# 2x3AND_OR_1.net
KiCad netlist of a schematic drawn in EAGLE
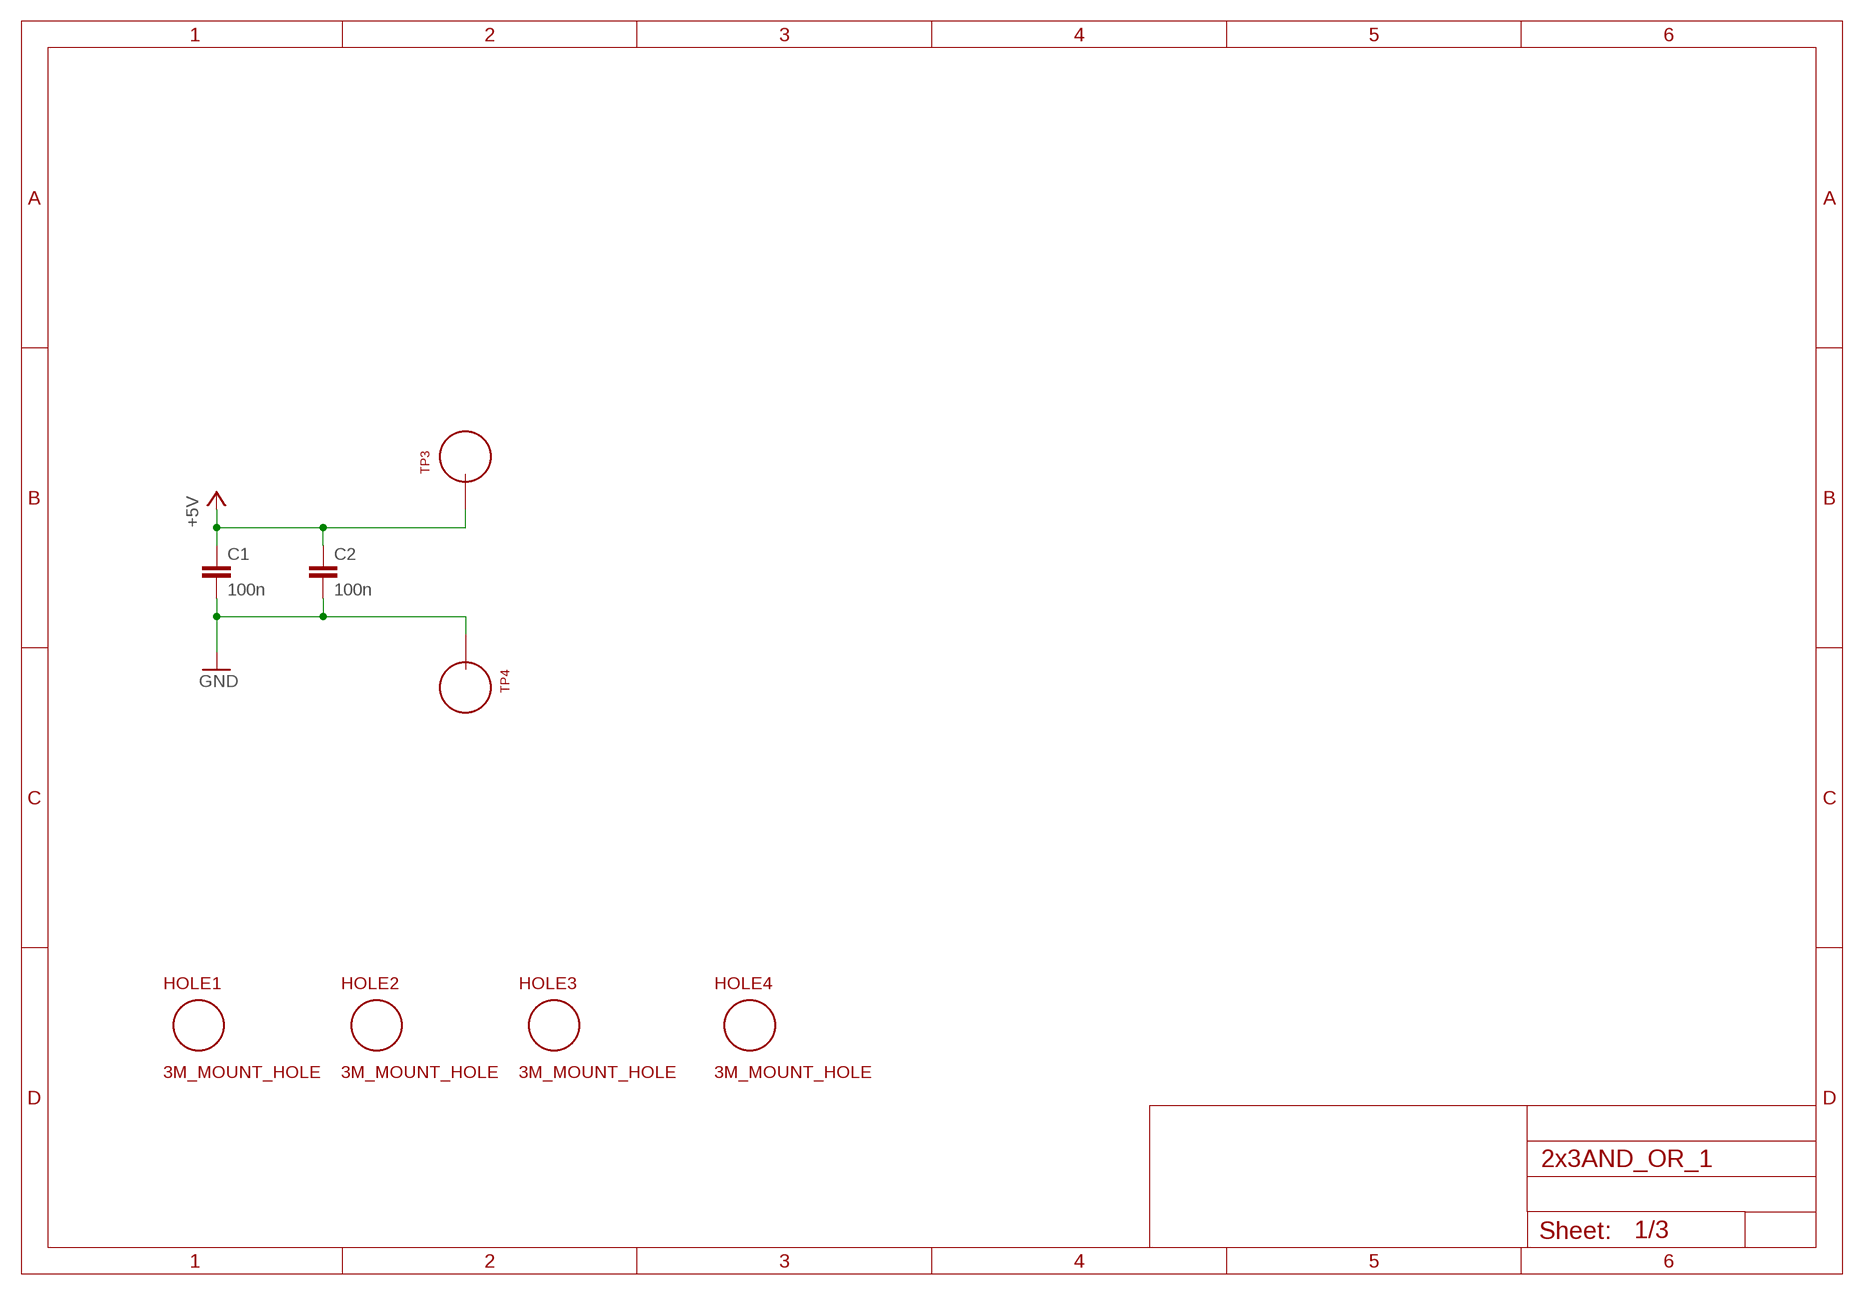
[diagram p0: schematic, sheet 1]
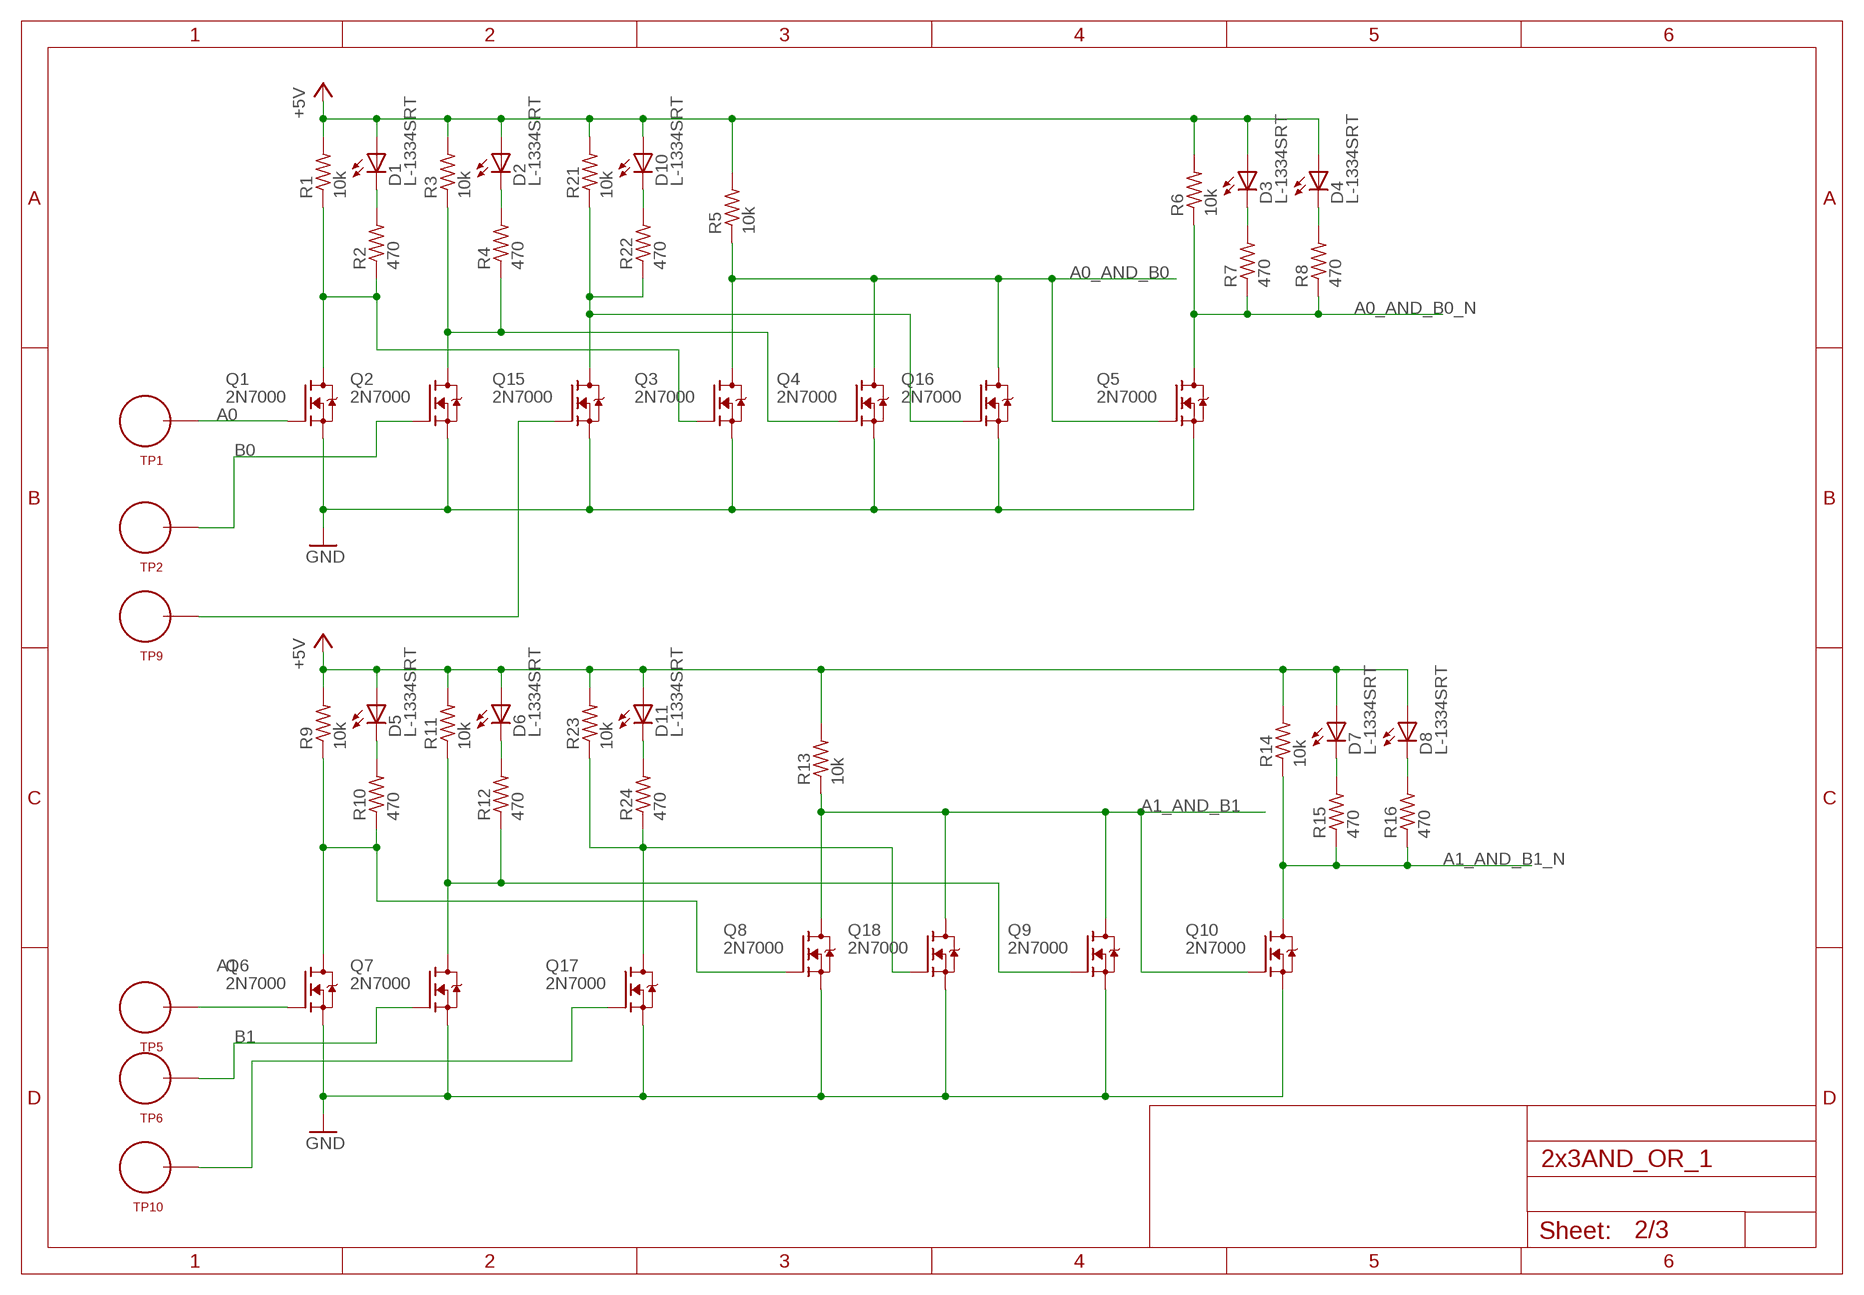
[diagram p1: schematic, sheet 2]
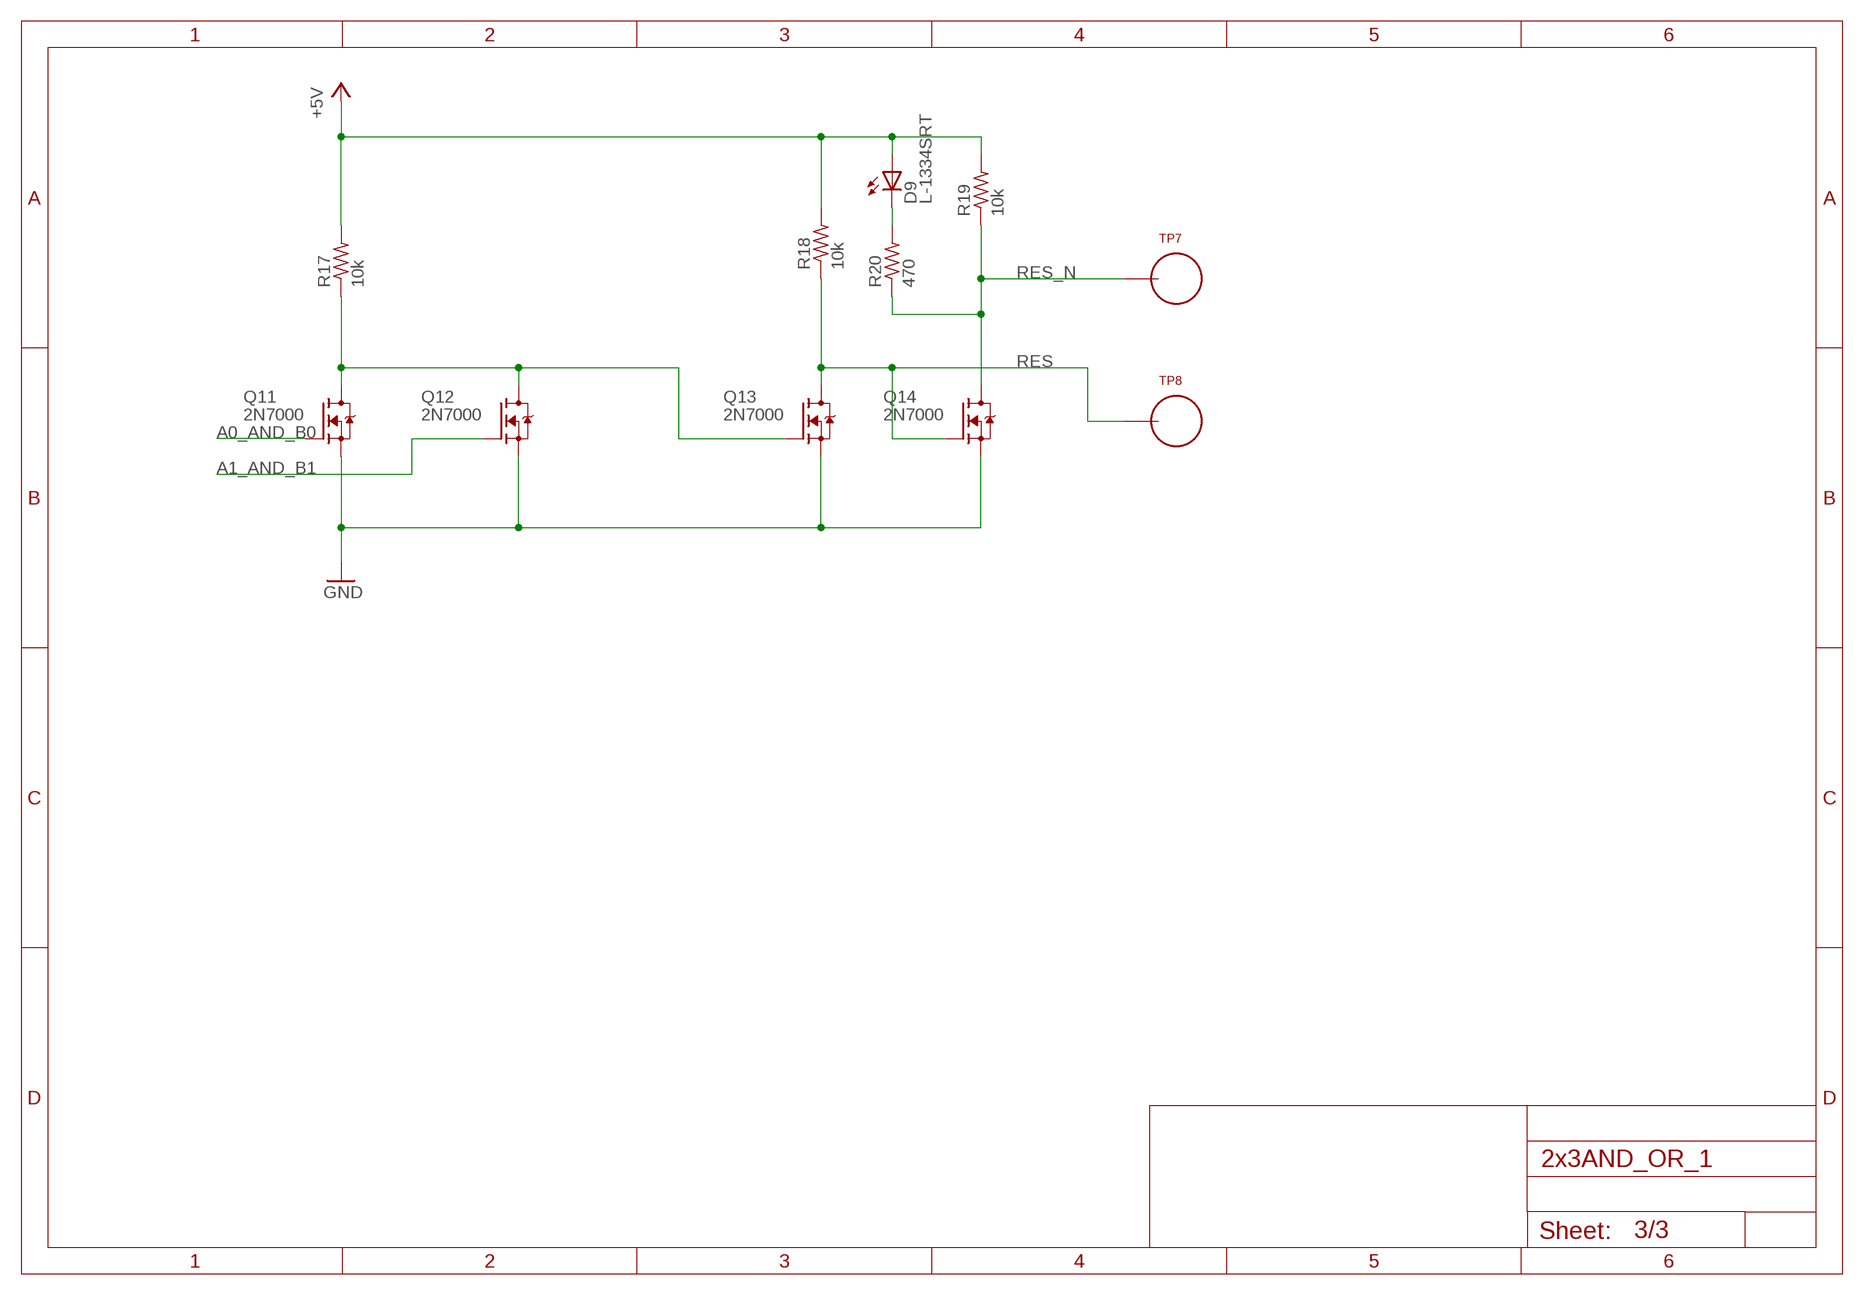
[diagram p2: schematic, sheet 3]

(export (version "E")
  (design (tool "Eeschema 10.0.6"))
  (components
    (comp (ref "D1")
      (value "L-1334SRT")
      (footprint "eagle-import:LED3MM")
      (libsource (lib "eagle-import") (part "L-1334SRT"))
    )
    (comp (ref "D2")
      (value "L-1334SRT")
      (footprint "eagle-import:LED3MM")
      (libsource (lib "eagle-import") (part "L-1334SRT"))
    )
    (comp (ref "D3")
      (value "L-1334SRT")
      (footprint "eagle-import:LED3MM")
      (libsource (lib "eagle-import") (part "L-1334SRT"))
    )
    (comp (ref "D4")
      (value "L-1334SRT")
      (footprint "eagle-import:LED3MM")
      (libsource (lib "eagle-import") (part "L-1334SRT"))
    )
    (comp (ref "D5")
      (value "L-1334SRT")
      (footprint "eagle-import:LED3MM")
      (libsource (lib "eagle-import") (part "L-1334SRT"))
    )
    (comp (ref "D6")
      (value "L-1334SRT")
      (footprint "eagle-import:LED3MM")
      (libsource (lib "eagle-import") (part "L-1334SRT"))
    )
    (comp (ref "D7")
      (value "L-1334SRT")
      (footprint "eagle-import:LED3MM")
      (libsource (lib "eagle-import") (part "L-1334SRT"))
    )
    (comp (ref "D8")
      (value "L-1334SRT")
      (footprint "eagle-import:LED3MM")
      (libsource (lib "eagle-import") (part "L-1334SRT"))
    )
    (comp (ref "D10")
      (value "L-1334SRT")
      (footprint "eagle-import:LED3MM")
      (libsource (lib "eagle-import") (part "L-1334SRT"))
    )
    (comp (ref "D11")
      (value "L-1334SRT")
      (footprint "eagle-import:LED3MM")
      (libsource (lib "eagle-import") (part "L-1334SRT"))
    )
    (comp (ref "Q1")
      (value "2N7000")
      (footprint "eagle-import:TO92-DGS")
      (libsource (lib "eagle-import") (part "2N7000"))
    )
    (comp (ref "Q2")
      (value "2N7000")
      (footprint "eagle-import:TO92-DGS")
      (libsource (lib "eagle-import") (part "2N7000"))
    )
    (comp (ref "Q3")
      (value "2N7000")
      (footprint "eagle-import:TO92-DGS")
      (libsource (lib "eagle-import") (part "2N7000"))
    )
    (comp (ref "Q4")
      (value "2N7000")
      (footprint "eagle-import:TO92-DGS")
      (libsource (lib "eagle-import") (part "2N7000"))
    )
    (comp (ref "Q5")
      (value "2N7000")
      (footprint "eagle-import:TO92-DGS")
      (libsource (lib "eagle-import") (part "2N7000"))
    )
    (comp (ref "Q6")
      (value "2N7000")
      (footprint "eagle-import:TO92-DGS")
      (libsource (lib "eagle-import") (part "2N7000"))
    )
    (comp (ref "Q7")
      (value "2N7000")
      (footprint "eagle-import:TO92-DGS")
      (libsource (lib "eagle-import") (part "2N7000"))
    )
    (comp (ref "Q8")
      (value "2N7000")
      (footprint "eagle-import:TO92-DGS")
      (libsource (lib "eagle-import") (part "2N7000"))
    )
    (comp (ref "Q9")
      (value "2N7000")
      (footprint "eagle-import:TO92-DGS")
      (libsource (lib "eagle-import") (part "2N7000"))
    )
    (comp (ref "Q10")
      (value "2N7000")
      (footprint "eagle-import:TO92-DGS")
      (libsource (lib "eagle-import") (part "2N7000"))
    )
    (comp (ref "Q15")
      (value "2N7000")
      (footprint "eagle-import:TO92-DGS")
      (libsource (lib "eagle-import") (part "2N7000"))
    )
    (comp (ref "Q16")
      (value "2N7000")
      (footprint "eagle-import:TO92-DGS")
      (libsource (lib "eagle-import") (part "2N7000"))
    )
    (comp (ref "Q17")
      (value "2N7000")
      (footprint "eagle-import:TO92-DGS")
      (libsource (lib "eagle-import") (part "2N7000"))
    )
    (comp (ref "Q18")
      (value "2N7000")
      (footprint "eagle-import:TO92-DGS")
      (libsource (lib "eagle-import") (part "2N7000"))
    )
    (comp (ref "R1")
      (value "10k")
      (footprint "eagle-import:R_P2INCH")
      (libsource (lib "eagle-import") (part "R_P2INCH"))
    )
    (comp (ref "R2")
      (value "470")
      (footprint "eagle-import:R_P2INCH")
      (libsource (lib "eagle-import") (part "R_P2INCH"))
    )
    (comp (ref "R3")
      (value "10k")
      (footprint "eagle-import:R_P2INCH")
      (libsource (lib "eagle-import") (part "R_P2INCH"))
    )
    (comp (ref "R4")
      (value "470")
      (footprint "eagle-import:R_P2INCH")
      (libsource (lib "eagle-import") (part "R_P2INCH"))
    )
    (comp (ref "R5")
      (value "10k")
      (footprint "eagle-import:R_P2INCH")
      (libsource (lib "eagle-import") (part "R_P2INCH"))
    )
    (comp (ref "R6")
      (value "10k")
      (footprint "eagle-import:R_P2INCH")
      (libsource (lib "eagle-import") (part "R_P2INCH"))
    )
    (comp (ref "R7")
      (value "470")
      (footprint "eagle-import:R_P2INCH")
      (libsource (lib "eagle-import") (part "R_P2INCH"))
    )
    (comp (ref "R8")
      (value "470")
      (footprint "eagle-import:R_P2INCH")
      (libsource (lib "eagle-import") (part "R_P2INCH"))
    )
    (comp (ref "R9")
      (value "10k")
      (footprint "eagle-import:R_P2INCH")
      (libsource (lib "eagle-import") (part "R_P2INCH"))
    )
    (comp (ref "R10")
      (value "470")
      (footprint "eagle-import:R_P2INCH")
      (libsource (lib "eagle-import") (part "R_P2INCH"))
    )
    (comp (ref "R11")
      (value "10k")
      (footprint "eagle-import:R_P2INCH")
      (libsource (lib "eagle-import") (part "R_P2INCH"))
    )
    (comp (ref "R12")
      (value "470")
      (footprint "eagle-import:R_P2INCH")
      (libsource (lib "eagle-import") (part "R_P2INCH"))
    )
    (comp (ref "R13")
      (value "10k")
      (footprint "eagle-import:R_P2INCH")
      (libsource (lib "eagle-import") (part "R_P2INCH"))
    )
    (comp (ref "R14")
      (value "10k")
      (footprint "eagle-import:R_P2INCH")
      (libsource (lib "eagle-import") (part "R_P2INCH"))
    )
    (comp (ref "R15")
      (value "470")
      (footprint "eagle-import:R_P2INCH")
      (libsource (lib "eagle-import") (part "R_P2INCH"))
    )
    (comp (ref "R16")
      (value "470")
      (footprint "eagle-import:R_P2INCH")
      (libsource (lib "eagle-import") (part "R_P2INCH"))
    )
    (comp (ref "R21")
      (value "10k")
      (footprint "eagle-import:R_P2INCH")
      (libsource (lib "eagle-import") (part "R_P2INCH"))
    )
    (comp (ref "R22")
      (value "470")
      (footprint "eagle-import:R_P2INCH")
      (libsource (lib "eagle-import") (part "R_P2INCH"))
    )
    (comp (ref "R23")
      (value "10k")
      (footprint "eagle-import:R_P2INCH")
      (libsource (lib "eagle-import") (part "R_P2INCH"))
    )
    (comp (ref "R24")
      (value "470")
      (footprint "eagle-import:R_P2INCH")
      (libsource (lib "eagle-import") (part "R_P2INCH"))
    )
    (comp (ref "TP1")
      (value "TEST_LOOP")
      (footprint "eagle-import:TEST_LOOP")
      (libsource (lib "eagle-import") (part "TEST_LOOP"))
    )
    (comp (ref "TP2")
      (value "TEST_LOOP")
      (footprint "eagle-import:TEST_LOOP")
      (libsource (lib "eagle-import") (part "TEST_LOOP"))
    )
    (comp (ref "TP5")
      (value "TEST_LOOP")
      (footprint "eagle-import:TEST_LOOP")
      (libsource (lib "eagle-import") (part "TEST_LOOP"))
    )
    (comp (ref "TP6")
      (value "TEST_LOOP")
      (footprint "eagle-import:TEST_LOOP")
      (libsource (lib "eagle-import") (part "TEST_LOOP"))
    )
    (comp (ref "TP9")
      (value "TEST_LOOP")
      (footprint "eagle-import:TEST_LOOP")
      (libsource (lib "eagle-import") (part "TEST_LOOP"))
    )
    (comp (ref "TP10")
      (value "TEST_LOOP")
      (footprint "eagle-import:TEST_LOOP")
      (libsource (lib "eagle-import") (part "TEST_LOOP"))
    )
    (comp (ref "D9")
      (value "L-1334SRT")
      (footprint "eagle-import:LED3MM")
      (libsource (lib "eagle-import") (part "L-1334SRT"))
    )
    (comp (ref "Q11")
      (value "2N7000")
      (footprint "eagle-import:TO92-DGS")
      (libsource (lib "eagle-import") (part "2N7000"))
    )
    (comp (ref "Q12")
      (value "2N7000")
      (footprint "eagle-import:TO92-DGS")
      (libsource (lib "eagle-import") (part "2N7000"))
    )
    (comp (ref "Q13")
      (value "2N7000")
      (footprint "eagle-import:TO92-DGS")
      (libsource (lib "eagle-import") (part "2N7000"))
    )
    (comp (ref "Q14")
      (value "2N7000")
      (footprint "eagle-import:TO92-DGS")
      (libsource (lib "eagle-import") (part "2N7000"))
    )
    (comp (ref "R17")
      (value "10k")
      (footprint "eagle-import:R_P2INCH")
      (libsource (lib "eagle-import") (part "R_P2INCH"))
    )
    (comp (ref "R18")
      (value "10k")
      (footprint "eagle-import:R_P2INCH")
      (libsource (lib "eagle-import") (part "R_P2INCH"))
    )
    (comp (ref "R19")
      (value "10k")
      (footprint "eagle-import:R_P2INCH")
      (libsource (lib "eagle-import") (part "R_P2INCH"))
    )
    (comp (ref "R20")
      (value "470")
      (footprint "eagle-import:R_P2INCH")
      (libsource (lib "eagle-import") (part "R_P2INCH"))
    )
    (comp (ref "TP7")
      (value "TEST_LOOP")
      (footprint "eagle-import:TEST_LOOP")
      (libsource (lib "eagle-import") (part "TEST_LOOP"))
    )
    (comp (ref "TP8")
      (value "TEST_LOOP")
      (footprint "eagle-import:TEST_LOOP")
      (libsource (lib "eagle-import") (part "TEST_LOOP"))
    )
    (comp (ref "C1")
      (value "100n")
      (footprint "eagle-import:CAP_P2INCH")
      (libsource (lib "eagle-import") (part "C_P2INCH"))
    )
    (comp (ref "C2")
      (value "100n")
      (footprint "eagle-import:CAP_P2INCH")
      (libsource (lib "eagle-import") (part "C_P2INCH"))
    )
    (comp (ref "HOLE1")
      (value "3M_MOUNT_HOLE")
      (footprint "eagle-import:3M_HOLE")
      (libsource (lib "eagle-import") (part "3M_MOUNT_HOLE"))
    )
    (comp (ref "HOLE2")
      (value "3M_MOUNT_HOLE")
      (footprint "eagle-import:3M_HOLE")
      (libsource (lib "eagle-import") (part "3M_MOUNT_HOLE"))
    )
    (comp (ref "HOLE3")
      (value "3M_MOUNT_HOLE")
      (footprint "eagle-import:3M_HOLE")
      (libsource (lib "eagle-import") (part "3M_MOUNT_HOLE"))
    )
    (comp (ref "HOLE4")
      (value "3M_MOUNT_HOLE")
      (footprint "eagle-import:3M_HOLE")
      (libsource (lib "eagle-import") (part "3M_MOUNT_HOLE"))
    )
    (comp (ref "TP3")
      (value "TEST_LOOP")
      (footprint "eagle-import:TEST_LOOP")
      (libsource (lib "eagle-import") (part "TEST_LOOP"))
    )
    (comp (ref "TP4")
      (value "TEST_LOOP")
      (footprint "eagle-import:TEST_LOOP")
      (libsource (lib "eagle-import") (part "TEST_LOOP"))
    )
  )
  (nets
    (net (code "1") (name "+5V") (class "Default")
      (node (ref "C1") (pin "1") (pinfunction "1_1") (pintype "passive"))
      (node (ref "C2") (pin "1") (pinfunction "1_1") (pintype "passive"))
      (node (ref "D1") (pin "A") (pinfunction "A_A") (pintype "passive"))
      (node (ref "D10") (pin "A") (pinfunction "A_A") (pintype "passive"))
      (node (ref "D11") (pin "A") (pinfunction "A_A") (pintype "passive"))
      (node (ref "D2") (pin "A") (pinfunction "A_A") (pintype "passive"))
      (node (ref "D3") (pin "A") (pinfunction "A_A") (pintype "passive"))
      (node (ref "D4") (pin "A") (pinfunction "A_A") (pintype "passive"))
      (node (ref "D5") (pin "A") (pinfunction "A_A") (pintype "passive"))
      (node (ref "D6") (pin "A") (pinfunction "A_A") (pintype "passive"))
      (node (ref "D7") (pin "A") (pinfunction "A_A") (pintype "passive"))
      (node (ref "D8") (pin "A") (pinfunction "A_A") (pintype "passive"))
      (node (ref "D9") (pin "A") (pinfunction "A_A") (pintype "passive"))
      (node (ref "R1") (pin "2") (pinfunction "2_2") (pintype "passive"))
      (node (ref "R11") (pin "2") (pinfunction "2_2") (pintype "passive"))
      (node (ref "R13") (pin "2") (pinfunction "2_2") (pintype "passive"))
      (node (ref "R14") (pin "2") (pinfunction "2_2") (pintype "passive"))
      (node (ref "R17") (pin "2") (pinfunction "2_2") (pintype "passive"))
      (node (ref "R18") (pin "2") (pinfunction "2_2") (pintype "passive"))
      (node (ref "R19") (pin "2") (pinfunction "2_2") (pintype "passive"))
      (node (ref "R21") (pin "2") (pinfunction "2_2") (pintype "passive"))
      (node (ref "R23") (pin "2") (pinfunction "2_2") (pintype "passive"))
      (node (ref "R3") (pin "2") (pinfunction "2_2") (pintype "passive"))
      (node (ref "R5") (pin "2") (pinfunction "2_2") (pintype "passive"))
      (node (ref "R6") (pin "2") (pinfunction "2_2") (pintype "passive"))
      (node (ref "R9") (pin "2") (pinfunction "2_2") (pintype "passive"))
      (node (ref "TP3") (pin "P$1") (pinfunction "P$1_P$1") (pintype "bidirectional"))
    )
    (net (code "2") (name "A0") (class "Default")
      (node (ref "Q1") (pin "G") (pinfunction "G_G") (pintype "passive"))
      (node (ref "TP1") (pin "P$1") (pinfunction "P$1_P$1") (pintype "bidirectional"))
    )
    (net (code "3") (name "A0_AND_B0") (class "Default")
      (node (ref "Q11") (pin "G") (pinfunction "G_G") (pintype "passive"))
      (node (ref "Q16") (pin "D") (pinfunction "D_D") (pintype "passive"))
      (node (ref "Q3") (pin "D") (pinfunction "D_D") (pintype "passive"))
      (node (ref "Q4") (pin "D") (pinfunction "D_D") (pintype "passive"))
      (node (ref "Q5") (pin "G") (pinfunction "G_G") (pintype "passive"))
      (node (ref "R5") (pin "1") (pinfunction "1_1") (pintype "passive"))
    )
    (net (code "4") (name "A0_AND_B0_N") (class "Default")
      (node (ref "Q5") (pin "D") (pinfunction "D_D") (pintype "passive"))
      (node (ref "R6") (pin "1") (pinfunction "1_1") (pintype "passive"))
      (node (ref "R7") (pin "1") (pinfunction "1_1") (pintype "passive"))
      (node (ref "R8") (pin "1") (pinfunction "1_1") (pintype "passive"))
    )
    (net (code "5") (name "A1") (class "Default")
      (node (ref "Q6") (pin "G") (pinfunction "G_G") (pintype "passive"))
      (node (ref "TP5") (pin "P$1") (pinfunction "P$1_P$1") (pintype "bidirectional"))
    )
    (net (code "6") (name "A1_AND_B1") (class "Default")
      (node (ref "Q10") (pin "G") (pinfunction "G_G") (pintype "passive"))
      (node (ref "Q12") (pin "G") (pinfunction "G_G") (pintype "passive"))
      (node (ref "Q18") (pin "D") (pinfunction "D_D") (pintype "passive"))
      (node (ref "Q8") (pin "D") (pinfunction "D_D") (pintype "passive"))
      (node (ref "Q9") (pin "D") (pinfunction "D_D") (pintype "passive"))
      (node (ref "R13") (pin "1") (pinfunction "1_1") (pintype "passive"))
    )
    (net (code "7") (name "A1_AND_B1_N") (class "Default")
      (node (ref "Q10") (pin "D") (pinfunction "D_D") (pintype "passive"))
      (node (ref "R14") (pin "1") (pinfunction "1_1") (pintype "passive"))
      (node (ref "R15") (pin "1") (pinfunction "1_1") (pintype "passive"))
      (node (ref "R16") (pin "1") (pinfunction "1_1") (pintype "passive"))
    )
    (net (code "8") (name "B0") (class "Default")
      (node (ref "Q2") (pin "G") (pinfunction "G_G") (pintype "passive"))
      (node (ref "TP2") (pin "P$1") (pinfunction "P$1_P$1") (pintype "bidirectional"))
    )
    (net (code "9") (name "B1") (class "Default")
      (node (ref "Q7") (pin "G") (pinfunction "G_G") (pintype "passive"))
      (node (ref "TP6") (pin "P$1") (pinfunction "P$1_P$1") (pintype "bidirectional"))
    )
    (net (code "10") (name "GND") (class "Default")
      (node (ref "C1") (pin "2") (pinfunction "2_2") (pintype "passive"))
      (node (ref "C2") (pin "2") (pinfunction "2_2") (pintype "passive"))
      (node (ref "Q1") (pin "S") (pinfunction "S_S") (pintype "passive"))
      (node (ref "Q10") (pin "S") (pinfunction "S_S") (pintype "passive"))
      (node (ref "Q11") (pin "S") (pinfunction "S_S") (pintype "passive"))
      (node (ref "Q12") (pin "S") (pinfunction "S_S") (pintype "passive"))
      (node (ref "Q13") (pin "S") (pinfunction "S_S") (pintype "passive"))
      (node (ref "Q14") (pin "S") (pinfunction "S_S") (pintype "passive"))
      (node (ref "Q15") (pin "S") (pinfunction "S_S") (pintype "passive"))
      (node (ref "Q16") (pin "S") (pinfunction "S_S") (pintype "passive"))
      (node (ref "Q17") (pin "S") (pinfunction "S_S") (pintype "passive"))
      (node (ref "Q18") (pin "S") (pinfunction "S_S") (pintype "passive"))
      (node (ref "Q2") (pin "S") (pinfunction "S_S") (pintype "passive"))
      (node (ref "Q3") (pin "S") (pinfunction "S_S") (pintype "passive"))
      (node (ref "Q4") (pin "S") (pinfunction "S_S") (pintype "passive"))
      (node (ref "Q5") (pin "S") (pinfunction "S_S") (pintype "passive"))
      (node (ref "Q6") (pin "S") (pinfunction "S_S") (pintype "passive"))
      (node (ref "Q7") (pin "S") (pinfunction "S_S") (pintype "passive"))
      (node (ref "Q8") (pin "S") (pinfunction "S_S") (pintype "passive"))
      (node (ref "Q9") (pin "S") (pinfunction "S_S") (pintype "passive"))
      (node (ref "TP4") (pin "P$1") (pinfunction "P$1_P$1") (pintype "bidirectional"))
    )
    (net (code "11") (name "Net-(D1-C)") (class "Default")
      (node (ref "D1") (pin "K") (pinfunction "C_K") (pintype "passive"))
      (node (ref "R2") (pin "2") (pinfunction "2_2") (pintype "passive"))
    )
    (net (code "12") (name "Net-(D2-C)") (class "Default")
      (node (ref "D2") (pin "K") (pinfunction "C_K") (pintype "passive"))
      (node (ref "R4") (pin "2") (pinfunction "2_2") (pintype "passive"))
    )
    (net (code "13") (name "Net-(D3-C)") (class "Default")
      (node (ref "D3") (pin "K") (pinfunction "C_K") (pintype "passive"))
      (node (ref "R7") (pin "2") (pinfunction "2_2") (pintype "passive"))
    )
    (net (code "14") (name "Net-(D4-C)") (class "Default")
      (node (ref "D4") (pin "K") (pinfunction "C_K") (pintype "passive"))
      (node (ref "R8") (pin "2") (pinfunction "2_2") (pintype "passive"))
    )
    (net (code "15") (name "Net-(D5-C)") (class "Default")
      (node (ref "D5") (pin "K") (pinfunction "C_K") (pintype "passive"))
      (node (ref "R10") (pin "2") (pinfunction "2_2") (pintype "passive"))
    )
    (net (code "16") (name "Net-(D6-C)") (class "Default")
      (node (ref "D6") (pin "K") (pinfunction "C_K") (pintype "passive"))
      (node (ref "R12") (pin "2") (pinfunction "2_2") (pintype "passive"))
    )
    (net (code "17") (name "Net-(D7-C)") (class "Default")
      (node (ref "D7") (pin "K") (pinfunction "C_K") (pintype "passive"))
      (node (ref "R15") (pin "2") (pinfunction "2_2") (pintype "passive"))
    )
    (net (code "18") (name "Net-(D8-C)") (class "Default")
      (node (ref "D8") (pin "K") (pinfunction "C_K") (pintype "passive"))
      (node (ref "R16") (pin "2") (pinfunction "2_2") (pintype "passive"))
    )
    (net (code "19") (name "Net-(D9-C)") (class "Default")
      (node (ref "D9") (pin "K") (pinfunction "C_K") (pintype "passive"))
      (node (ref "R20") (pin "2") (pinfunction "2_2") (pintype "passive"))
    )
    (net (code "20") (name "Net-(D10-C)") (class "Default")
      (node (ref "D10") (pin "K") (pinfunction "C_K") (pintype "passive"))
      (node (ref "R22") (pin "2") (pinfunction "2_2") (pintype "passive"))
    )
    (net (code "21") (name "Net-(D11-C)") (class "Default")
      (node (ref "D11") (pin "K") (pinfunction "C_K") (pintype "passive"))
      (node (ref "R24") (pin "2") (pinfunction "2_2") (pintype "passive"))
    )
    (net (code "22") (name "Net-(Q1-PadD)") (class "Default")
      (node (ref "Q1") (pin "D") (pinfunction "D_D") (pintype "passive"))
      (node (ref "Q3") (pin "G") (pinfunction "G_G") (pintype "passive"))
      (node (ref "R1") (pin "1") (pinfunction "1_1") (pintype "passive"))
      (node (ref "R2") (pin "1") (pinfunction "1_1") (pintype "passive"))
    )
    (net (code "23") (name "Net-(Q2-PadD)") (class "Default")
      (node (ref "Q2") (pin "D") (pinfunction "D_D") (pintype "passive"))
      (node (ref "Q4") (pin "G") (pinfunction "G_G") (pintype "passive"))
      (node (ref "R3") (pin "1") (pinfunction "1_1") (pintype "passive"))
      (node (ref "R4") (pin "1") (pinfunction "1_1") (pintype "passive"))
    )
    (net (code "24") (name "Net-(Q6-PadD)") (class "Default")
      (node (ref "Q6") (pin "D") (pinfunction "D_D") (pintype "passive"))
      (node (ref "Q8") (pin "G") (pinfunction "G_G") (pintype "passive"))
      (node (ref "R10") (pin "1") (pinfunction "1_1") (pintype "passive"))
      (node (ref "R9") (pin "1") (pinfunction "1_1") (pintype "passive"))
    )
    (net (code "25") (name "Net-(Q7-PadD)") (class "Default")
      (node (ref "Q7") (pin "D") (pinfunction "D_D") (pintype "passive"))
      (node (ref "Q9") (pin "G") (pinfunction "G_G") (pintype "passive"))
      (node (ref "R11") (pin "1") (pinfunction "1_1") (pintype "passive"))
      (node (ref "R12") (pin "1") (pinfunction "1_1") (pintype "passive"))
    )
    (net (code "26") (name "Net-(Q11-PadD)") (class "Default")
      (node (ref "Q11") (pin "D") (pinfunction "D_D") (pintype "passive"))
      (node (ref "Q12") (pin "D") (pinfunction "D_D") (pintype "passive"))
      (node (ref "Q13") (pin "G") (pinfunction "G_G") (pintype "passive"))
      (node (ref "R17") (pin "1") (pinfunction "1_1") (pintype "passive"))
    )
    (net (code "27") (name "Net-(Q15-PadD)") (class "Default")
      (node (ref "Q15") (pin "D") (pinfunction "D_D") (pintype "passive"))
      (node (ref "Q16") (pin "G") (pinfunction "G_G") (pintype "passive"))
      (node (ref "R21") (pin "1") (pinfunction "1_1") (pintype "passive"))
      (node (ref "R22") (pin "1") (pinfunction "1_1") (pintype "passive"))
    )
    (net (code "28") (name "Net-(Q15-PadG)") (class "Default")
      (node (ref "Q15") (pin "G") (pinfunction "G_G") (pintype "passive"))
      (node (ref "TP9") (pin "P$1") (pinfunction "P$1_P$1") (pintype "bidirectional"))
    )
    (net (code "29") (name "Net-(Q17-PadD)") (class "Default")
      (node (ref "Q17") (pin "D") (pinfunction "D_D") (pintype "passive"))
      (node (ref "Q18") (pin "G") (pinfunction "G_G") (pintype "passive"))
      (node (ref "R23") (pin "1") (pinfunction "1_1") (pintype "passive"))
      (node (ref "R24") (pin "1") (pinfunction "1_1") (pintype "passive"))
    )
    (net (code "30") (name "Net-(Q17-PadG)") (class "Default")
      (node (ref "Q17") (pin "G") (pinfunction "G_G") (pintype "passive"))
      (node (ref "TP10") (pin "P$1") (pinfunction "P$1_P$1") (pintype "bidirectional"))
    )
    (net (code "31") (name "RES") (class "Default")
      (node (ref "Q13") (pin "D") (pinfunction "D_D") (pintype "passive"))
      (node (ref "Q14") (pin "G") (pinfunction "G_G") (pintype "passive"))
      (node (ref "R18") (pin "1") (pinfunction "1_1") (pintype "passive"))
      (node (ref "TP8") (pin "P$1") (pinfunction "P$1_P$1") (pintype "bidirectional"))
    )
    (net (code "32") (name "RES_N") (class "Default")
      (node (ref "Q14") (pin "D") (pinfunction "D_D") (pintype "passive"))
      (node (ref "R19") (pin "1") (pinfunction "1_1") (pintype "passive"))
      (node (ref "R20") (pin "1") (pinfunction "1_1") (pintype "passive"))
      (node (ref "TP7") (pin "P$1") (pinfunction "P$1_P$1") (pintype "bidirectional"))
    )
  )
)
